# APP_UD_new.net
KiCad netlist of a schematic drawn in EAGLE
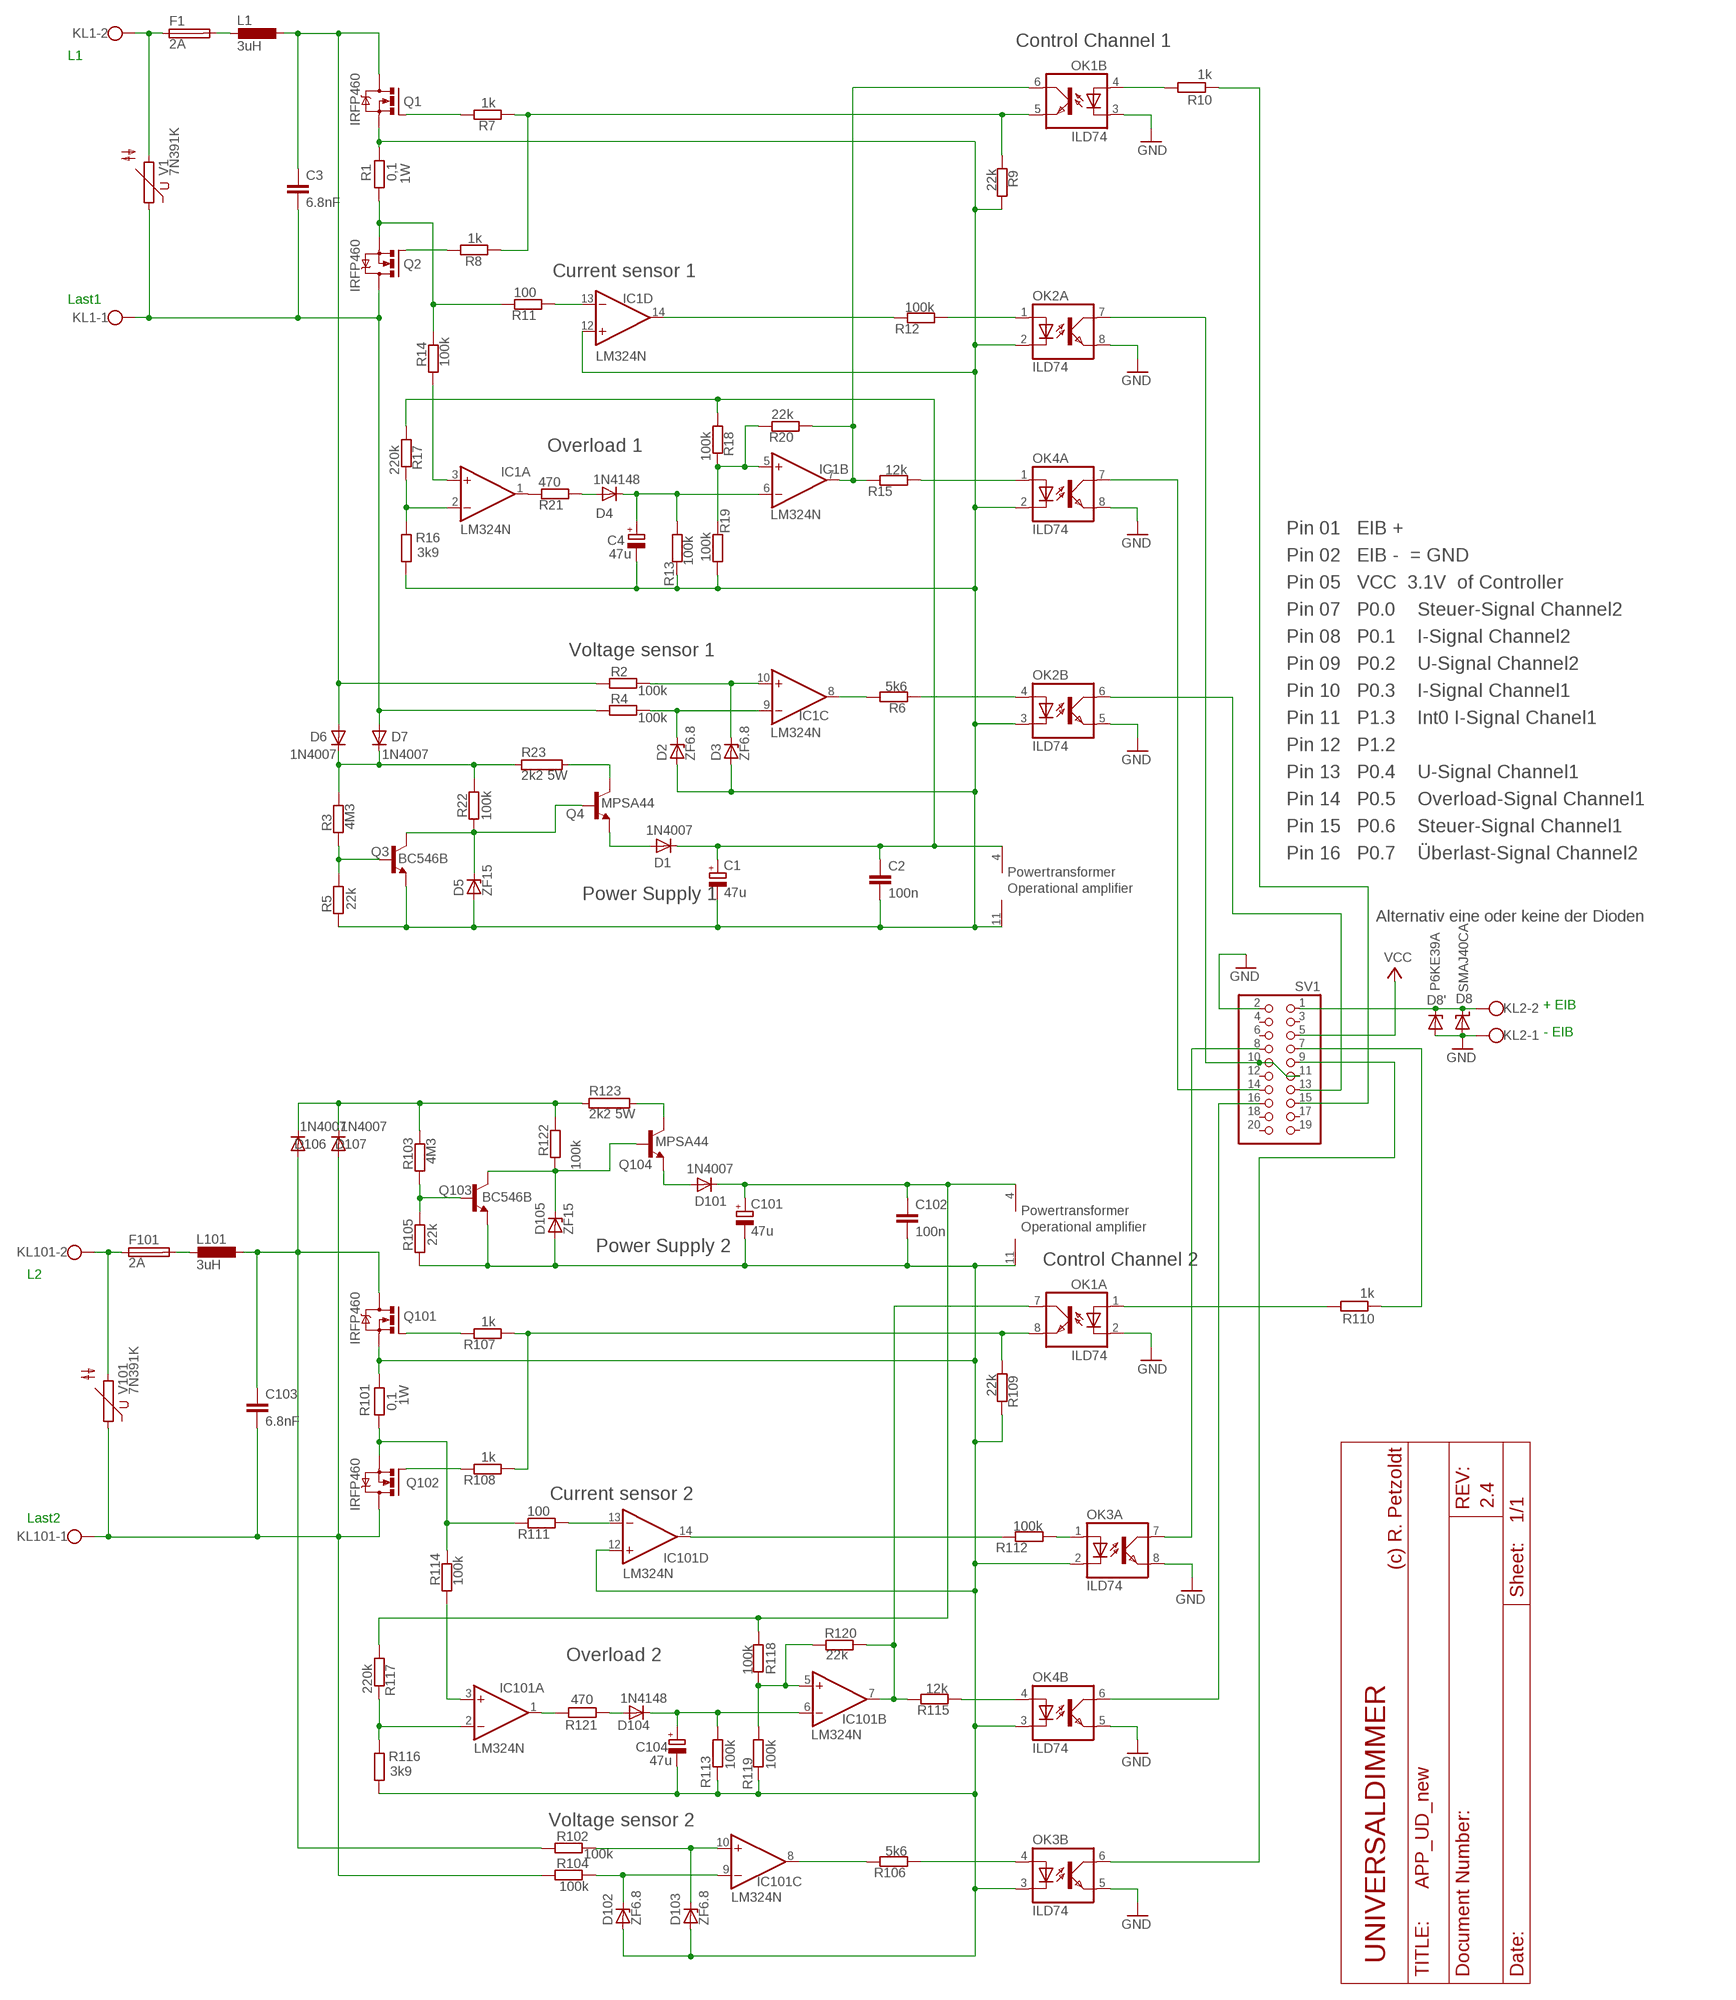
[diagram p0: schematic, sheet 1]

(export (version "E")
  (design (tool "Eeschema 10.0.6"))
  (components
    (comp (ref "C1")
      (value "47u")
      (footprint "eagle-import:E2-5")
      (libsource (lib "eagle-import") (part "CPOL-EUE2-5"))
    )
    (comp (ref "C2")
      (value "100n")
      (footprint "eagle-import:C025-030X050")
      (libsource (lib "eagle-import") (part "C-EU025-030X050"))
    )
    (comp (ref "C3")
      (value "6.8nF")
      (footprint "eagle-import:C050-075X075")
      (libsource (lib "eagle-import") (part "C-EU050-075X075"))
    )
    (comp (ref "C4")
      (value "47u")
      (footprint "eagle-import:E2-5")
      (libsource (lib "eagle-import") (part "CPOL-EUE2-5"))
    )
    (comp (ref "C101")
      (value "47u")
      (footprint "eagle-import:E2-5")
      (libsource (lib "eagle-import") (part "CPOL-EUE2-5"))
    )
    (comp (ref "C102")
      (value "100n")
      (footprint "eagle-import:C025-030X050")
      (libsource (lib "eagle-import") (part "C-EU025-030X050"))
    )
    (comp (ref "C103")
      (value "6.8nF")
      (footprint "eagle-import:C050-075X075")
      (libsource (lib "eagle-import") (part "C-EU050-075X075"))
    )
    (comp (ref "C104")
      (value "47u")
      (footprint "eagle-import:E2-5")
      (libsource (lib "eagle-import") (part "CPOL-EUE2-5"))
    )
    (comp (ref "D1")
      (value "1N4007")
      (footprint "eagle-import:D-7")
      (libsource (lib "eagle-import") (part "1N4148DO35-7S"))
    )
    (comp (ref "D2")
      (value "ZF6.8")
      (footprint "eagle-import:ZDIO-5")
      (libsource (lib "eagle-import") (part "ZENER-DIODEZD-5"))
    )
    (comp (ref "D3")
      (value "ZF6.8")
      (footprint "eagle-import:ZDIO-7.5")
      (libsource (lib "eagle-import") (part "ZENER-DIODEZD-7.5"))
    )
    (comp (ref "D4")
      (value "1N4148")
      (footprint "eagle-import:D-7")
      (libsource (lib "eagle-import") (part "1N4148DO35-7S"))
    )
    (comp (ref "D5")
      (value "ZF15")
      (footprint "eagle-import:ZDIO-7.5")
      (libsource (lib "eagle-import") (part "ZENER-DIODEZD-7.5"))
    )
    (comp (ref "D6")
      (value "1N4007")
      (footprint "eagle-import:D-7.5")
      (libsource (lib "eagle-import") (part "DIODE-D-7.5"))
    )
    (comp (ref "D7")
      (value "1N4007")
      (footprint "eagle-import:D-7.5")
      (libsource (lib "eagle-import") (part "DIODE-D-7.5"))
    )
    (comp (ref "D8")
      (value "SMAJ40CA")
      (footprint "eagle-import:SMBJ")
      (libsource (lib "eagle-import") (part "SUPPRESSOR-SMBJ"))
    )
    (comp (ref "D8'")
      (value "P6KE39A")
      (footprint "eagle-import:ZDIO-7.5")
      (libsource (lib "eagle-import") (part "ZENER-DIODEZD-7.5"))
    )
    (comp (ref "D101")
      (value "1N4007")
      (footprint "eagle-import:D-7")
      (libsource (lib "eagle-import") (part "1N4148DO35-7S"))
    )
    (comp (ref "D102")
      (value "ZF6.8")
      (footprint "eagle-import:ZDIO-5")
      (libsource (lib "eagle-import") (part "ZENER-DIODEZD-5"))
    )
    (comp (ref "D103")
      (value "ZF6.8")
      (footprint "eagle-import:ZDIO-7.5")
      (libsource (lib "eagle-import") (part "ZENER-DIODEZD-7.5"))
    )
    (comp (ref "D104")
      (value "1N4148")
      (footprint "eagle-import:D-7")
      (libsource (lib "eagle-import") (part "1N4148DO35-7S"))
    )
    (comp (ref "D105")
      (value "ZF15")
      (footprint "eagle-import:ZDIO-7.5")
      (libsource (lib "eagle-import") (part "ZENER-DIODEZD-7.5"))
    )
    (comp (ref "D106")
      (value "1N4007")
      (footprint "eagle-import:D-7.5")
      (libsource (lib "eagle-import") (part "DIODE-D-7.5"))
    )
    (comp (ref "D107")
      (value "1N4007")
      (footprint "eagle-import:D-7.5")
      (libsource (lib "eagle-import") (part "DIODE-D-7.5"))
    )
    (comp (ref "F1")
      (value "2A")
      (footprint "eagle-import:TR5")
      (libsource (lib "eagle-import") (part "TR5"))
    )
    (comp (ref "F101")
      (value "2A")
      (footprint "eagle-import:TR5")
      (libsource (lib "eagle-import") (part "TR5"))
    )
    (comp (ref "IC1")
      (value "LM324N")
      (footprint "eagle-import:DIL14")
      (libsource (lib "eagle-import") (part "LM324N"))
    )
    (comp (ref "IC101")
      (value "LM324N")
      (footprint "eagle-import:DIL14")
      (libsource (lib "eagle-import") (part "LM324N"))
    )
    (comp (ref "KL1")
      (value "W237-102")
      (footprint "eagle-import:W237-102")
      (libsource (lib "eagle-import") (part "W237-102"))
    )
    (comp (ref "KL2")
      (value "W237-102")
      (footprint "eagle-import:W237-102")
      (libsource (lib "eagle-import") (part "W237-102"))
    )
    (comp (ref "KL101")
      (value "W237-102")
      (footprint "eagle-import:W237-102")
      (libsource (lib "eagle-import") (part "W237-102"))
    )
    (comp (ref "L1")
      (value "3uH")
      (footprint "eagle-import:0414V")
      (libsource (lib "eagle-import") (part "L-EU414V"))
    )
    (comp (ref "L101")
      (value "3uH")
      (footprint "eagle-import:0414V")
      (libsource (lib "eagle-import") (part "L-EU414V"))
    )
    (comp (ref "OK1")
      (value "ILD74")
      (footprint "eagle-import:DIL08")
      (libsource (lib "eagle-import") (part "ILD2"))
    )
    (comp (ref "OK2")
      (value "ILD74")
      (footprint "eagle-import:DIL08")
      (libsource (lib "eagle-import") (part "ILD2"))
    )
    (comp (ref "OK3")
      (value "ILD74")
      (footprint "eagle-import:DIL08")
      (libsource (lib "eagle-import") (part "ILD2"))
    )
    (comp (ref "OK4")
      (value "ILD74")
      (footprint "eagle-import:DIL08")
      (libsource (lib "eagle-import") (part "ILD2"))
    )
    (comp (ref "Q1")
      (value "IRFP460")
      (footprint "eagle-import:TO247BV")
      (libsource (lib "eagle-import") (part "IRFPC40"))
    )
    (comp (ref "Q2")
      (value "IRFP460")
      (footprint "eagle-import:TO247BV")
      (libsource (lib "eagle-import") (part "IRFPC40"))
    )
    (comp (ref "Q3")
      (value "BC546B")
      (footprint "eagle-import:TO92-EBC")
      (libsource (lib "eagle-import") (part "BC546B"))
    )
    (comp (ref "Q4")
      (value "MPSA44")
      (footprint "eagle-import:TO92-EBC")
      (libsource (lib "eagle-import") (part "-NPN-TO92-EBCMPSA44"))
    )
    (comp (ref "Q101")
      (value "IRFP460")
      (footprint "eagle-import:TO247BV")
      (libsource (lib "eagle-import") (part "IRFPC40"))
    )
    (comp (ref "Q102")
      (value "IRFP460")
      (footprint "eagle-import:TO247BV")
      (libsource (lib "eagle-import") (part "IRFPC40"))
    )
    (comp (ref "Q103")
      (value "BC546B")
      (footprint "eagle-import:TO92-EBC")
      (libsource (lib "eagle-import") (part "BC546B"))
    )
    (comp (ref "Q104")
      (value "MPSA44")
      (footprint "eagle-import:TO92-EBC")
      (libsource (lib "eagle-import") (part "-NPN-TO92-EBCMPSA44"))
    )
    (comp (ref "R1")
      (value "0,1")
      (footprint "eagle-import:0414V")
      (libsource (lib "eagle-import") (part "R-EU_0414/5V"))
    )
    (comp (ref "R2")
      (value "100k")
      (footprint "eagle-import:0204_7")
      (libsource (lib "eagle-import") (part "R-EU_0204/7"))
    )
    (comp (ref "R3")
      (value "4M3")
      (footprint "eagle-import:0204_7")
      (libsource (lib "eagle-import") (part "R-EU_0204/7"))
    )
    (comp (ref "R4")
      (value "100k")
      (footprint "eagle-import:0204_7")
      (libsource (lib "eagle-import") (part "R-EU_0204/7"))
    )
    (comp (ref "R5")
      (value "22k")
      (footprint "eagle-import:0204_7")
      (libsource (lib "eagle-import") (part "R-EU_0204/7"))
    )
    (comp (ref "R6")
      (value "5k6")
      (footprint "eagle-import:0204_7")
      (libsource (lib "eagle-import") (part "R-EU_0204/7"))
    )
    (comp (ref "R7")
      (value "1k")
      (footprint "eagle-import:0204_7")
      (libsource (lib "eagle-import") (part "R-EU_0204/7"))
    )
    (comp (ref "R8")
      (value "1k")
      (footprint "eagle-import:0204_7")
      (libsource (lib "eagle-import") (part "R-EU_0204/7"))
    )
    (comp (ref "R9")
      (value "22k")
      (footprint "eagle-import:0204_7")
      (libsource (lib "eagle-import") (part "R-EU_0204/7"))
    )
    (comp (ref "R10")
      (value "1k")
      (footprint "eagle-import:0204_7")
      (libsource (lib "eagle-import") (part "R-EU_0204/7"))
    )
    (comp (ref "R11")
      (value "100")
      (footprint "eagle-import:0204_7")
      (libsource (lib "eagle-import") (part "R-EU_0204/7"))
    )
    (comp (ref "R12")
      (value "100k")
      (footprint "eagle-import:0204_7")
      (libsource (lib "eagle-import") (part "R-EU_0204/7"))
    )
    (comp (ref "R13")
      (value "100k")
      (footprint "eagle-import:0204_7")
      (libsource (lib "eagle-import") (part "R-EU_0204/7"))
    )
    (comp (ref "R14")
      (value "100k")
      (footprint "eagle-import:0204_7")
      (libsource (lib "eagle-import") (part "R-EU_0204/7"))
    )
    (comp (ref "R15")
      (value "12k")
      (footprint "eagle-import:0204_7")
      (libsource (lib "eagle-import") (part "R-EU_0204/7"))
    )
    (comp (ref "R16")
      (value "3k9")
      (footprint "eagle-import:0204_7")
      (libsource (lib "eagle-import") (part "R-EU_0204/7"))
    )
    (comp (ref "R17")
      (value "220k")
      (footprint "eagle-import:0204_7")
      (libsource (lib "eagle-import") (part "R-EU_0204/7"))
    )
    (comp (ref "R18")
      (value "100k")
      (footprint "eagle-import:0204_7")
      (libsource (lib "eagle-import") (part "R-EU_0204/7"))
    )
    (comp (ref "R19")
      (value "100k")
      (footprint "eagle-import:0204_7")
      (libsource (lib "eagle-import") (part "R-EU_0204/7"))
    )
    (comp (ref "R20")
      (value "22k")
      (footprint "eagle-import:0204_7")
      (libsource (lib "eagle-import") (part "R-EU_0204/7"))
    )
    (comp (ref "R21")
      (value "470")
      (footprint "eagle-import:0204_7")
      (libsource (lib "eagle-import") (part "R-EU_0204/7"))
    )
    (comp (ref "R22")
      (value "100k")
      (footprint "eagle-import:0204_7")
      (libsource (lib "eagle-import") (part "R-EU_0204/7"))
    )
    (comp (ref "R23")
      (value "2k2 5W")
      (footprint "eagle-import:KH208-8_10B")
      (libsource (lib "eagle-import") (part "R"))
    )
    (comp (ref "R101")
      (value "0,1")
      (footprint "eagle-import:0414V")
      (libsource (lib "eagle-import") (part "R-EU_0414/5V"))
    )
    (comp (ref "R102")
      (value "100k")
      (footprint "eagle-import:0204_7")
      (libsource (lib "eagle-import") (part "R-EU_0204/7"))
    )
    (comp (ref "R103")
      (value "4M3")
      (footprint "eagle-import:0204_7")
      (libsource (lib "eagle-import") (part "R-EU_0204/7"))
    )
    (comp (ref "R104")
      (value "100k")
      (footprint "eagle-import:0204_7")
      (libsource (lib "eagle-import") (part "R-EU_0204/7"))
    )
    (comp (ref "R105")
      (value "22k")
      (footprint "eagle-import:0204_7")
      (libsource (lib "eagle-import") (part "R-EU_0204/7"))
    )
    (comp (ref "R106")
      (value "5k6")
      (footprint "eagle-import:0204_7")
      (libsource (lib "eagle-import") (part "R-EU_0204/7"))
    )
    (comp (ref "R107")
      (value "1k")
      (footprint "eagle-import:0204_7")
      (libsource (lib "eagle-import") (part "R-EU_0204/7"))
    )
    (comp (ref "R108")
      (value "1k")
      (footprint "eagle-import:0204_7")
      (libsource (lib "eagle-import") (part "R-EU_0204/7"))
    )
    (comp (ref "R109")
      (value "22k")
      (footprint "eagle-import:0204_7")
      (libsource (lib "eagle-import") (part "R-EU_0204/7"))
    )
    (comp (ref "R110")
      (value "1k")
      (footprint "eagle-import:0204_7")
      (libsource (lib "eagle-import") (part "R-EU_0204/7"))
    )
    (comp (ref "R111")
      (value "100")
      (footprint "eagle-import:0204_7")
      (libsource (lib "eagle-import") (part "R-EU_0204/7"))
    )
    (comp (ref "R112")
      (value "100k")
      (footprint "eagle-import:0207_12")
      (libsource (lib "eagle-import") (part "R-EU_0207/12"))
    )
    (comp (ref "R113")
      (value "100k")
      (footprint "eagle-import:0204_7")
      (libsource (lib "eagle-import") (part "R-EU_0204/7"))
    )
    (comp (ref "R114")
      (value "100k")
      (footprint "eagle-import:0204_7")
      (libsource (lib "eagle-import") (part "R-EU_0204/7"))
    )
    (comp (ref "R115")
      (value "12k")
      (footprint "eagle-import:0204_7")
      (libsource (lib "eagle-import") (part "R-EU_0204/7"))
    )
    (comp (ref "R116")
      (value "3k9")
      (footprint "eagle-import:0204_7")
      (libsource (lib "eagle-import") (part "R-EU_0204/7"))
    )
    (comp (ref "R117")
      (value "220k")
      (footprint "eagle-import:0204_7")
      (libsource (lib "eagle-import") (part "R-EU_0204/7"))
    )
    (comp (ref "R118")
      (value "100k")
      (footprint "eagle-import:0204_7")
      (libsource (lib "eagle-import") (part "R-EU_0204/7"))
    )
    (comp (ref "R119")
      (value "100k")
      (footprint "eagle-import:0204_7")
      (libsource (lib "eagle-import") (part "R-EU_0204/7"))
    )
    (comp (ref "R120")
      (value "22k")
      (footprint "eagle-import:0204_7")
      (libsource (lib "eagle-import") (part "R-EU_0204/7"))
    )
    (comp (ref "R121")
      (value "470")
      (footprint "eagle-import:0204_7")
      (libsource (lib "eagle-import") (part "R-EU_0204/7"))
    )
    (comp (ref "R122")
      (value "100k")
      (footprint "eagle-import:0204_7")
      (libsource (lib "eagle-import") (part "R-EU_0204/7"))
    )
    (comp (ref "R123")
      (value "2k2 5W")
      (footprint "eagle-import:KH208-8_10B")
      (libsource (lib "eagle-import") (part "R"))
    )
    (comp (ref "SV1")
      (value "PINHD-2X10")
      (footprint "eagle-import:2X10")
      (libsource (lib "eagle-import") (part "PINHD-2X10"))
    )
    (comp (ref "V1")
      (value "7N391K")
      (footprint "eagle-import:S05K11")
      (libsource (lib "eagle-import") (part "S05K11"))
    )
    (comp (ref "V101")
      (value "7N391K")
      (footprint "eagle-import:S05K11")
      (libsource (lib "eagle-import") (part "S05K11"))
    )
  )
  (nets
    (net (code "1") (name "GND") (class "Default")
      (node (ref "D8") (pin "A") (pinfunction "A_A") (pintype "passive"))
      (node (ref "D8'") (pin "A") (pinfunction "A_A") (pintype "passive"))
      (node (ref "KL2") (pin "1") (pinfunction "KL_1") (pintype "passive"))
      (node (ref "OK1") (pin "2") (pinfunction "C_2") (pintype "passive"))
      (node (ref "OK1") (pin "3") (pinfunction "C_3") (pintype "passive"))
      (node (ref "OK2") (pin "5") (pinfunction "EMIT_5") (pintype "passive"))
      (node (ref "OK2") (pin "8") (pinfunction "EMIT_8") (pintype "passive"))
      (node (ref "OK3") (pin "5") (pinfunction "EMIT_5") (pintype "passive"))
      (node (ref "OK3") (pin "8") (pinfunction "EMIT_8") (pintype "passive"))
      (node (ref "OK4") (pin "5") (pinfunction "EMIT_5") (pintype "passive"))
      (node (ref "OK4") (pin "8") (pinfunction "EMIT_8") (pintype "passive"))
      (node (ref "SV1") (pin "2") (pinfunction "2_2") (pintype "passive"))
    )
    (net (code "2") (name "Net-(C3-Pad1)") (class "Default")
      (node (ref "C3") (pin "1") (pinfunction "1_1") (pintype "passive"))
      (node (ref "D6") (pin "A") (pinfunction "A_A") (pintype "passive"))
      (node (ref "L1") (pin "1") (pinfunction "1_1") (pintype "passive"))
      (node (ref "Q1") (pin "D") (pinfunction "D_D") (pintype "passive"))
      (node (ref "R2") (pin "1") (pinfunction "1_1") (pintype "passive"))
    )
    (net (code "3") (name "Net-(C103-Pad1)") (class "Default")
      (node (ref "C103") (pin "1") (pinfunction "1_1") (pintype "passive"))
      (node (ref "D106") (pin "A") (pinfunction "A_A") (pintype "passive"))
      (node (ref "L101") (pin "1") (pinfunction "1_1") (pintype "passive"))
      (node (ref "Q101") (pin "D") (pinfunction "D_D") (pintype "passive"))
      (node (ref "R102") (pin "1") (pinfunction "1_1") (pintype "passive"))
    )
    (net (code "4") (name "Net-(D1-PadA)") (class "Default")
      (node (ref "D1") (pin "A") (pinfunction "A_A") (pintype "passive"))
      (node (ref "Q4") (pin "E") (pinfunction "E_E") (pintype "passive"))
    )
    (net (code "5") (name "Net-(D4-PadA)") (class "Default")
      (node (ref "D4") (pin "A") (pinfunction "A_A") (pintype "passive"))
      (node (ref "R21") (pin "1") (pinfunction "1_1") (pintype "passive"))
    )
    (net (code "6") (name "Net-(D5-PadC)") (class "Default")
      (node (ref "D5") (pin "C") (pinfunction "C_C") (pintype "passive"))
      (node (ref "Q3") (pin "C") (pinfunction "C_C") (pintype "passive"))
      (node (ref "Q4") (pin "B") (pinfunction "B_B") (pintype "passive"))
      (node (ref "R22") (pin "1") (pinfunction "1_1") (pintype "passive"))
    )
    (net (code "7") (name "Net-(D101-PadA)") (class "Default")
      (node (ref "D101") (pin "A") (pinfunction "A_A") (pintype "passive"))
      (node (ref "Q104") (pin "E") (pinfunction "E_E") (pintype "passive"))
    )
    (net (code "8") (name "Net-(D104-PadA)") (class "Default")
      (node (ref "D104") (pin "A") (pinfunction "A_A") (pintype "passive"))
      (node (ref "R121") (pin "1") (pinfunction "1_1") (pintype "passive"))
    )
    (net (code "9") (name "Net-(D105-PadC)") (class "Default")
      (node (ref "D105") (pin "C") (pinfunction "C_C") (pintype "passive"))
      (node (ref "Q103") (pin "C") (pinfunction "C_C") (pintype "passive"))
      (node (ref "Q104") (pin "B") (pinfunction "B_B") (pintype "passive"))
      (node (ref "R122") (pin "1") (pinfunction "1_1") (pintype "passive"))
    )
    (net (code "10") (name "Net-(F1-Pad2)") (class "Default")
      (node (ref "F1") (pin "2") (pinfunction "2_2") (pintype "passive"))
      (node (ref "L1") (pin "2") (pinfunction "2_2") (pintype "passive"))
    )
    (net (code "11") (name "Net-(F101-Pad2)") (class "Default")
      (node (ref "F101") (pin "2") (pinfunction "2_2") (pintype "passive"))
      (node (ref "L101") (pin "2") (pinfunction "2_2") (pintype "passive"))
    )
    (net (code "12") (name "Net-(IC1A-+IN)") (class "Default")
      (node (ref "IC1") (pin "3") (pinfunction "+IN_3") (pintype "input"))
      (node (ref "R14") (pin "1") (pinfunction "1_1") (pintype "passive"))
    )
    (net (code "13") (name "Net-(IC1A--IN)") (class "Default")
      (node (ref "IC1") (pin "2") (pinfunction "-IN_2") (pintype "input"))
      (node (ref "R16") (pin "1") (pinfunction "1_1") (pintype "passive"))
      (node (ref "R17") (pin "2") (pinfunction "2_2") (pintype "passive"))
    )
    (net (code "14") (name "Net-(IC1A-OUT)") (class "Default")
      (node (ref "IC1") (pin "1") (pinfunction "OUT_1") (pintype "output"))
      (node (ref "R21") (pin "2") (pinfunction "2_2") (pintype "passive"))
    )
    (net (code "15") (name "Net-(IC1B-+IN)") (class "Default")
      (node (ref "IC1") (pin "5") (pinfunction "+IN_5") (pintype "input"))
      (node (ref "R18") (pin "2") (pinfunction "2_2") (pintype "passive"))
      (node (ref "R19") (pin "2") (pinfunction "2_2") (pintype "passive"))
      (node (ref "R20") (pin "2") (pinfunction "2_2") (pintype "passive"))
    )
    (net (code "16") (name "Net-(IC1B--IN)") (class "Default")
      (node (ref "C4") (pin "+") (pinfunction "+_+") (pintype "passive"))
      (node (ref "D4") (pin "C") (pinfunction "C_C") (pintype "passive"))
      (node (ref "IC1") (pin "6") (pinfunction "-IN_6") (pintype "input"))
      (node (ref "R13") (pin "1") (pinfunction "1_1") (pintype "passive"))
    )
    (net (code "17") (name "Net-(IC1B-OUT)") (class "Default")
      (node (ref "IC1") (pin "7") (pinfunction "OUT_7") (pintype "output"))
      (node (ref "OK1") (pin "6") (pinfunction "COL_6") (pintype "passive"))
      (node (ref "R15") (pin "2") (pinfunction "2_2") (pintype "passive"))
      (node (ref "R20") (pin "1") (pinfunction "1_1") (pintype "passive"))
    )
    (net (code "18") (name "Net-(IC1C-+IN)") (class "Default")
      (node (ref "D3") (pin "C") (pinfunction "C_C") (pintype "passive"))
      (node (ref "IC1") (pin "10") (pinfunction "+IN_10") (pintype "input"))
      (node (ref "R2") (pin "2") (pinfunction "2_2") (pintype "passive"))
    )
    (net (code "19") (name "Net-(IC1C--IN)") (class "Default")
      (node (ref "D2") (pin "C") (pinfunction "C_C") (pintype "passive"))
      (node (ref "IC1") (pin "9") (pinfunction "-IN_9") (pintype "input"))
      (node (ref "R4") (pin "2") (pinfunction "2_2") (pintype "passive"))
    )
    (net (code "20") (name "Net-(IC1C-OUT)") (class "Default")
      (node (ref "IC1") (pin "8") (pinfunction "OUT_8") (pintype "output"))
      (node (ref "R6") (pin "2") (pinfunction "2_2") (pintype "passive"))
    )
    (net (code "21") (name "Net-(IC1D-+IN)") (class "Default")
      (node (ref "C1") (pin "-") (pinfunction "-_-") (pintype "passive"))
      (node (ref "C2") (pin "2") (pinfunction "2_2") (pintype "passive"))
      (node (ref "C4") (pin "-") (pinfunction "-_-") (pintype "passive"))
      (node (ref "D2") (pin "A") (pinfunction "A_A") (pintype "passive"))
      (node (ref "D3") (pin "A") (pinfunction "A_A") (pintype "passive"))
      (node (ref "D5") (pin "A") (pinfunction "A_A") (pintype "passive"))
      (node (ref "IC1") (pin "11") (pinfunction "V-_11") (pintype "power_in"))
      (node (ref "IC1") (pin "12") (pinfunction "+IN_12") (pintype "input"))
      (node (ref "OK2") (pin "2") (pinfunction "C_2") (pintype "passive"))
      (node (ref "OK2") (pin "3") (pinfunction "C_3") (pintype "passive"))
      (node (ref "OK4") (pin "2") (pinfunction "C_2") (pintype "passive"))
      (node (ref "Q1") (pin "S") (pinfunction "S_S") (pintype "passive"))
      (node (ref "Q3") (pin "E") (pinfunction "E_E") (pintype "passive"))
      (node (ref "R1") (pin "2") (pinfunction "2_2") (pintype "passive"))
      (node (ref "R13") (pin "2") (pinfunction "2_2") (pintype "passive"))
      (node (ref "R16") (pin "2") (pinfunction "2_2") (pintype "passive"))
      (node (ref "R19") (pin "1") (pinfunction "1_1") (pintype "passive"))
      (node (ref "R5") (pin "1") (pinfunction "1_1") (pintype "passive"))
      (node (ref "R9") (pin "2") (pinfunction "2_2") (pintype "passive"))
    )
    (net (code "22") (name "Net-(IC1D--IN)") (class "Default")
      (node (ref "IC1") (pin "13") (pinfunction "-IN_13") (pintype "input"))
      (node (ref "R11") (pin "1") (pinfunction "1_1") (pintype "passive"))
    )
    (net (code "23") (name "Net-(IC1D-OUT)") (class "Default")
      (node (ref "IC1") (pin "14") (pinfunction "OUT_14") (pintype "output"))
      (node (ref "R12") (pin "2") (pinfunction "2_2") (pintype "passive"))
    )
    (net (code "24") (name "Net-(IC1E-V+)") (class "Default")
      (node (ref "C1") (pin "+") (pinfunction "+_+") (pintype "passive"))
      (node (ref "C2") (pin "1") (pinfunction "1_1") (pintype "passive"))
      (node (ref "D1") (pin "C") (pinfunction "C_C") (pintype "passive"))
      (node (ref "IC1") (pin "4") (pinfunction "V+_4") (pintype "power_in"))
      (node (ref "R17") (pin "1") (pinfunction "1_1") (pintype "passive"))
      (node (ref "R18") (pin "1") (pinfunction "1_1") (pintype "passive"))
    )
    (net (code "25") (name "Net-(IC101A-+IN)") (class "Default")
      (node (ref "IC101") (pin "3") (pinfunction "+IN_3") (pintype "input"))
      (node (ref "R114") (pin "1") (pinfunction "1_1") (pintype "passive"))
    )
    (net (code "26") (name "Net-(IC101A--IN)") (class "Default")
      (node (ref "IC101") (pin "2") (pinfunction "-IN_2") (pintype "input"))
      (node (ref "R116") (pin "1") (pinfunction "1_1") (pintype "passive"))
      (node (ref "R117") (pin "2") (pinfunction "2_2") (pintype "passive"))
    )
    (net (code "27") (name "Net-(IC101A-OUT)") (class "Default")
      (node (ref "IC101") (pin "1") (pinfunction "OUT_1") (pintype "output"))
      (node (ref "R121") (pin "2") (pinfunction "2_2") (pintype "passive"))
    )
    (net (code "28") (name "Net-(IC101B-+IN)") (class "Default")
      (node (ref "IC101") (pin "5") (pinfunction "+IN_5") (pintype "input"))
      (node (ref "R118") (pin "2") (pinfunction "2_2") (pintype "passive"))
      (node (ref "R119") (pin "1") (pinfunction "1_1") (pintype "passive"))
      (node (ref "R120") (pin "1") (pinfunction "1_1") (pintype "passive"))
    )
    (net (code "29") (name "Net-(IC101B--IN)") (class "Default")
      (node (ref "C104") (pin "+") (pinfunction "+_+") (pintype "passive"))
      (node (ref "D104") (pin "C") (pinfunction "C_C") (pintype "passive"))
      (node (ref "IC101") (pin "6") (pinfunction "-IN_6") (pintype "input"))
      (node (ref "R113") (pin "1") (pinfunction "1_1") (pintype "passive"))
    )
    (net (code "30") (name "Net-(IC101B-OUT)") (class "Default")
      (node (ref "IC101") (pin "7") (pinfunction "OUT_7") (pintype "output"))
      (node (ref "OK1") (pin "7") (pinfunction "COL_7") (pintype "passive"))
      (node (ref "R115") (pin "2") (pinfunction "2_2") (pintype "passive"))
      (node (ref "R120") (pin "2") (pinfunction "2_2") (pintype "passive"))
    )
    (net (code "31") (name "Net-(IC101C-+IN)") (class "Default")
      (node (ref "D103") (pin "C") (pinfunction "C_C") (pintype "passive"))
      (node (ref "IC101") (pin "10") (pinfunction "+IN_10") (pintype "input"))
      (node (ref "R102") (pin "2") (pinfunction "2_2") (pintype "passive"))
    )
    (net (code "32") (name "Net-(IC101C--IN)") (class "Default")
      (node (ref "D102") (pin "C") (pinfunction "C_C") (pintype "passive"))
      (node (ref "IC101") (pin "9") (pinfunction "-IN_9") (pintype "input"))
      (node (ref "R104") (pin "2") (pinfunction "2_2") (pintype "passive"))
    )
    (net (code "33") (name "Net-(IC101C-OUT)") (class "Default")
      (node (ref "IC101") (pin "8") (pinfunction "OUT_8") (pintype "output"))
      (node (ref "R106") (pin "2") (pinfunction "2_2") (pintype "passive"))
    )
    (net (code "34") (name "Net-(IC101D-+IN)") (class "Default")
      (node (ref "C101") (pin "-") (pinfunction "-_-") (pintype "passive"))
      (node (ref "C102") (pin "2") (pinfunction "2_2") (pintype "passive"))
      (node (ref "C104") (pin "-") (pinfunction "-_-") (pintype "passive"))
      (node (ref "D102") (pin "A") (pinfunction "A_A") (pintype "passive"))
      (node (ref "D103") (pin "A") (pinfunction "A_A") (pintype "passive"))
      (node (ref "D105") (pin "A") (pinfunction "A_A") (pintype "passive"))
      (node (ref "IC101") (pin "11") (pinfunction "V-_11") (pintype "power_in"))
      (node (ref "IC101") (pin "12") (pinfunction "+IN_12") (pintype "input"))
      (node (ref "OK3") (pin "2") (pinfunction "C_2") (pintype "passive"))
      (node (ref "OK3") (pin "3") (pinfunction "C_3") (pintype "passive"))
      (node (ref "OK4") (pin "3") (pinfunction "C_3") (pintype "passive"))
      (node (ref "Q101") (pin "S") (pinfunction "S_S") (pintype "passive"))
      (node (ref "Q103") (pin "E") (pinfunction "E_E") (pintype "passive"))
      (node (ref "R101") (pin "2") (pinfunction "2_2") (pintype "passive"))
      (node (ref "R105") (pin "1") (pinfunction "1_1") (pintype "passive"))
      (node (ref "R109") (pin "2") (pinfunction "2_2") (pintype "passive"))
      (node (ref "R113") (pin "2") (pinfunction "2_2") (pintype "passive"))
      (node (ref "R116") (pin "2") (pinfunction "2_2") (pintype "passive"))
      (node (ref "R119") (pin "2") (pinfunction "2_2") (pintype "passive"))
    )
    (net (code "35") (name "Net-(IC101D--IN)") (class "Default")
      (node (ref "IC101") (pin "13") (pinfunction "-IN_13") (pintype "input"))
      (node (ref "R111") (pin "1") (pinfunction "1_1") (pintype "passive"))
    )
    (net (code "36") (name "Net-(IC101D-OUT)") (class "Default")
      (node (ref "IC101") (pin "14") (pinfunction "OUT_14") (pintype "output"))
      (node (ref "R112") (pin "2") (pinfunction "2_2") (pintype "passive"))
    )
    (net (code "37") (name "Net-(IC101E-V+)") (class "Default")
      (node (ref "C101") (pin "+") (pinfunction "+_+") (pintype "passive"))
      (node (ref "C102") (pin "1") (pinfunction "1_1") (pintype "passive"))
      (node (ref "D101") (pin "C") (pinfunction "C_C") (pintype "passive"))
      (node (ref "IC101") (pin "4") (pinfunction "V+_4") (pintype "power_in"))
      (node (ref "R117") (pin "1") (pinfunction "1_1") (pintype "passive"))
      (node (ref "R118") (pin "1") (pinfunction "1_1") (pintype "passive"))
    )
    (net (code "38") (name "Net-(KL1A-KL)") (class "Default")
      (node (ref "C3") (pin "2") (pinfunction "2_2") (pintype "passive"))
      (node (ref "D7") (pin "A") (pinfunction "A_A") (pintype "passive"))
      (node (ref "KL1") (pin "1") (pinfunction "KL_1") (pintype "passive"))
      (node (ref "Q2") (pin "D") (pinfunction "D_D") (pintype "passive"))
      (node (ref "R4") (pin "1") (pinfunction "1_1") (pintype "passive"))
      (node (ref "V1") (pin "1") (pinfunction "1_1") (pintype "passive"))
    )
    (net (code "39") (name "Net-(KL1B-KL)") (class "Default")
      (node (ref "F1") (pin "1") (pinfunction "1_1") (pintype "passive"))
      (node (ref "KL1") (pin "2") (pinfunction "KL_2") (pintype "passive"))
      (node (ref "V1") (pin "2") (pinfunction "2_2") (pintype "passive"))
    )
    (net (code "40") (name "Net-(KL2B-KL)") (class "Default")
      (node (ref "D8") (pin "C") (pinfunction "C_C") (pintype "passive"))
      (node (ref "D8'") (pin "C") (pinfunction "C_C") (pintype "passive"))
      (node (ref "KL2") (pin "2") (pinfunction "KL_2") (pintype "passive"))
      (node (ref "SV1") (pin "1") (pinfunction "1_1") (pintype "passive"))
    )
    (net (code "41") (name "Net-(KL101A-KL)") (class "Default")
      (node (ref "C103") (pin "2") (pinfunction "2_2") (pintype "passive"))
      (node (ref "D107") (pin "A") (pinfunction "A_A") (pintype "passive"))
      (node (ref "KL101") (pin "1") (pinfunction "KL_1") (pintype "passive"))
      (node (ref "Q102") (pin "D") (pinfunction "D_D") (pintype "passive"))
      (node (ref "R104") (pin "1") (pinfunction "1_1") (pintype "passive"))
      (node (ref "V101") (pin "1") (pinfunction "1_1") (pintype "passive"))
    )
    (net (code "42") (name "Net-(KL101B-KL)") (class "Default")
      (node (ref "F101") (pin "1") (pinfunction "1_1") (pintype "passive"))
      (node (ref "KL101") (pin "2") (pinfunction "KL_2") (pintype "passive"))
      (node (ref "V101") (pin "2") (pinfunction "2_2") (pintype "passive"))
    )
    (net (code "43") (name "Net-(OK1A-A)") (class "Default")
      (node (ref "OK1") (pin "1") (pinfunction "A_1") (pintype "passive"))
      (node (ref "R110") (pin "2") (pinfunction "2_2") (pintype "passive"))
    )
    (net (code "44") (name "Net-(OK1A-EMIT)") (class "Default")
      (node (ref "OK1") (pin "8") (pinfunction "EMIT_8") (pintype "passive"))
      (node (ref "R107") (pin "1") (pinfunction "1_1") (pintype "passive"))
      (node (ref "R108") (pin "1") (pinfunction "1_1") (pintype "passive"))
      (node (ref "R109") (pin "1") (pinfunction "1_1") (pintype "passive"))
    )
    (net (code "45") (name "Net-(OK1B-A)") (class "Default")
      (node (ref "OK1") (pin "4") (pinfunction "A_4") (pintype "passive"))
      (node (ref "R10") (pin "2") (pinfunction "2_2") (pintype "passive"))
    )
    (net (code "46") (name "Net-(OK1B-EMIT)") (class "Default")
      (node (ref "OK1") (pin "5") (pinfunction "EMIT_5") (pintype "passive"))
      (node (ref "R7") (pin "1") (pinfunction "1_1") (pintype "passive"))
      (node (ref "R8") (pin "1") (pinfunction "1_1") (pintype "passive"))
      (node (ref "R9") (pin "1") (pinfunction "1_1") (pintype "passive"))
    )
    (net (code "47") (name "Net-(OK2A-A)") (class "Default")
      (node (ref "OK2") (pin "1") (pinfunction "A_1") (pintype "passive"))
      (node (ref "R12") (pin "1") (pinfunction "1_1") (pintype "passive"))
    )
    (net (code "48") (name "Net-(OK2A-COL)") (class "Default")
      (node (ref "OK2") (pin "7") (pinfunction "COL_7") (pintype "passive"))
      (node (ref "SV1") (pin "10") (pinfunction "10_10") (pintype "passive"))
      (node (ref "SV1") (pin "11") (pinfunction "11_11") (pintype "passive"))
    )
    (net (code "49") (name "Net-(OK2B-A)") (class "Default")
      (node (ref "OK2") (pin "4") (pinfunction "A_4") (pintype "passive"))
      (node (ref "R6") (pin "1") (pinfunction "1_1") (pintype "passive"))
    )
    (net (code "50") (name "Net-(OK2B-COL)") (class "Default")
      (node (ref "OK2") (pin "6") (pinfunction "COL_6") (pintype "passive"))
      (node (ref "SV1") (pin "13") (pinfunction "13_13") (pintype "passive"))
    )
    (net (code "51") (name "Net-(OK3A-A)") (class "Default")
      (node (ref "OK3") (pin "1") (pinfunction "A_1") (pintype "passive"))
      (node (ref "R112") (pin "1") (pinfunction "1_1") (pintype "passive"))
    )
    (net (code "52") (name "Net-(OK3A-COL)") (class "Default")
      (node (ref "OK3") (pin "7") (pinfunction "COL_7") (pintype "passive"))
      (node (ref "SV1") (pin "8") (pinfunction "8_8") (pintype "passive"))
    )
    (net (code "53") (name "Net-(OK3B-A)") (class "Default")
      (node (ref "OK3") (pin "4") (pinfunction "A_4") (pintype "passive"))
      (node (ref "R106") (pin "1") (pinfunction "1_1") (pintype "passive"))
    )
    (net (code "54") (name "Net-(OK3B-COL)") (class "Default")
      (node (ref "OK3") (pin "6") (pinfunction "COL_6") (pintype "passive"))
      (node (ref "SV1") (pin "9") (pinfunction "9_9") (pintype "passive"))
    )
    (net (code "55") (name "Net-(OK4A-A)") (class "Default")
      (node (ref "OK4") (pin "1") (pinfunction "A_1") (pintype "passive"))
      (node (ref "R15") (pin "1") (pinfunction "1_1") (pintype "passive"))
    )
    (net (code "56") (name "Net-(OK4A-COL)") (class "Default")
      (node (ref "OK4") (pin "7") (pinfunction "COL_7") (pintype "passive"))
      (node (ref "SV1") (pin "14") (pinfunction "14_14") (pintype "passive"))
    )
    (net (code "57") (name "Net-(OK4B-A)") (class "Default")
      (node (ref "OK4") (pin "4") (pinfunction "A_4") (pintype "passive"))
      (node (ref "R115") (pin "1") (pinfunction "1_1") (pintype "passive"))
    )
    (net (code "58") (name "Net-(OK4B-COL)") (class "Default")
      (node (ref "OK4") (pin "6") (pinfunction "COL_6") (pintype "passive"))
      (node (ref "SV1") (pin "16") (pinfunction "16_16") (pintype "passive"))
    )
    (net (code "59") (name "Net-(Q1-PadG)") (class "Default")
      (node (ref "Q1") (pin "G") (pinfunction "G_G") (pintype "passive"))
      (node (ref "R7") (pin "2") (pinfunction "2_2") (pintype "passive"))
    )
    (net (code "60") (name "Net-(Q2-PadG)") (class "Default")
      (node (ref "Q2") (pin "G") (pinfunction "G_G") (pintype "passive"))
      (node (ref "R8") (pin "2") (pinfunction "2_2") (pintype "passive"))
    )
    (net (code "61") (name "Net-(Q2-PadS)") (class "Default")
      (node (ref "Q2") (pin "S") (pinfunction "S_S") (pintype "passive"))
      (node (ref "R1") (pin "1") (pinfunction "1_1") (pintype "passive"))
      (node (ref "R11") (pin "2") (pinfunction "2_2") (pintype "passive"))
      (node (ref "R14") (pin "2") (pinfunction "2_2") (pintype "passive"))
    )
    (net (code "62") (name "Net-(Q3-PadB)") (class "Default")
      (node (ref "Q3") (pin "B") (pinfunction "B_B") (pintype "passive"))
      (node (ref "R3") (pin "1") (pinfunction "1_1") (pintype "passive"))
      (node (ref "R5") (pin "2") (pinfunction "2_2") (pintype "passive"))
    )
    (net (code "63") (name "Net-(Q101-PadG)") (class "Default")
      (node (ref "Q101") (pin "G") (pinfunction "G_G") (pintype "passive"))
      (node (ref "R107") (pin "2") (pinfunction "2_2") (pintype "passive"))
    )
    (net (code "64") (name "Net-(Q102-PadG)") (class "Default")
      (node (ref "Q102") (pin "G") (pinfunction "G_G") (pintype "passive"))
      (node (ref "R108") (pin "2") (pinfunction "2_2") (pintype "passive"))
    )
    (net (code "65") (name "Net-(Q102-PadS)") (class "Default")
      (node (ref "Q102") (pin "S") (pinfunction "S_S") (pintype "passive"))
      (node (ref "R101") (pin "1") (pinfunction "1_1") (pintype "passive"))
      (node (ref "R111") (pin "2") (pinfunction "2_2") (pintype "passive"))
      (node (ref "R114") (pin "2") (pinfunction "2_2") (pintype "passive"))
    )
    (net (code "66") (name "Net-(Q103-PadB)") (class "Default")
      (node (ref "Q103") (pin "B") (pinfunction "B_B") (pintype "passive"))
      (node (ref "R103") (pin "1") (pinfunction "1_1") (pintype "passive"))
      (node (ref "R105") (pin "2") (pinfunction "2_2") (pintype "passive"))
    )
    (net (code "67") (name "Net-(R10-Pad1)") (class "Default")
      (node (ref "R10") (pin "1") (pinfunction "1_1") (pintype "passive"))
      (node (ref "SV1") (pin "15") (pinfunction "15_15") (pintype "passive"))
    )
    (net (code "68") (name "Net-(R23-1)") (class "Default")
      (node (ref "D6") (pin "C") (pinfunction "C_C") (pintype "passive"))
      (node (ref "D7") (pin "C") (pinfunction "C_C") (pintype "passive"))
      (node (ref "R22") (pin "2") (pinfunction "2_2") (pintype "passive"))
      (node (ref "R23") (pin "P$1") (pinfunction "1_P$1") (pintype "passive"))
      (node (ref "R3") (pin "2") (pinfunction "2_2") (pintype "passive"))
    )
    (net (code "69") (name "Net-(R23-2)") (class "Default")
      (node (ref "Q4") (pin "C") (pinfunction "C_C") (pintype "passive"))
      (node (ref "R23") (pin "P$2") (pinfunction "2_P$2") (pintype "passive"))
    )
    (net (code "70") (name "Net-(R110-Pad1)") (class "Default")
      (node (ref "R110") (pin "1") (pinfunction "1_1") (pintype "passive"))
      (node (ref "SV1") (pin "7") (pinfunction "7_7") (pintype "passive"))
    )
    (net (code "71") (name "Net-(R123-1)") (class "Default")
      (node (ref "D106") (pin "C") (pinfunction "C_C") (pintype "passive"))
      (node (ref "D107") (pin "C") (pinfunction "C_C") (pintype "passive"))
      (node (ref "R103") (pin "2") (pinfunction "2_2") (pintype "passive"))
      (node (ref "R122") (pin "2") (pinfunction "2_2") (pintype "passive"))
      (node (ref "R123") (pin "P$1") (pinfunction "1_P$1") (pintype "passive"))
    )
    (net (code "72") (name "Net-(R123-2)") (class "Default")
      (node (ref "Q104") (pin "C") (pinfunction "C_C") (pintype "passive"))
      (node (ref "R123") (pin "P$2") (pinfunction "2_P$2") (pintype "passive"))
    )
    (net (code "73") (name "VCC") (class "Default")
      (node (ref "SV1") (pin "5") (pinfunction "5_5") (pintype "passive"))
    )
    (net (code "74") (name "unconnected-(SV1-Pad3)") (class "Default")
      (node (ref "SV1") (pin "3") (pinfunction "3_3") (pintype "passive"))
    )
    (net (code "75") (name "unconnected-(SV1-Pad4)") (class "Default")
      (node (ref "SV1") (pin "4") (pinfunction "4_4") (pintype "passive"))
    )
    (net (code "76") (name "unconnected-(SV1-Pad6)") (class "Default")
      (node (ref "SV1") (pin "6") (pinfunction "6_6") (pintype "passive"))
    )
    (net (code "77") (name "unconnected-(SV1-Pad12)") (class "Default")
      (node (ref "SV1") (pin "12") (pinfunction "12_12") (pintype "passive"))
    )
    (net (code "78") (name "unconnected-(SV1-Pad17)") (class "Default")
      (node (ref "SV1") (pin "17") (pinfunction "17_17") (pintype "passive"))
    )
    (net (code "79") (name "unconnected-(SV1-Pad18)") (class "Default")
      (node (ref "SV1") (pin "18") (pinfunction "18_18") (pintype "passive"))
    )
    (net (code "80") (name "unconnected-(SV1-Pad19)") (class "Default")
      (node (ref "SV1") (pin "19") (pinfunction "19_19") (pintype "passive"))
    )
    (net (code "81") (name "unconnected-(SV1-Pad20)") (class "Default")
      (node (ref "SV1") (pin "20") (pinfunction "20_20") (pintype "passive"))
    )
  )
)
